# Balanced_Line_Receiver.net
KiCad netlist of a schematic drawn in Altium Designer
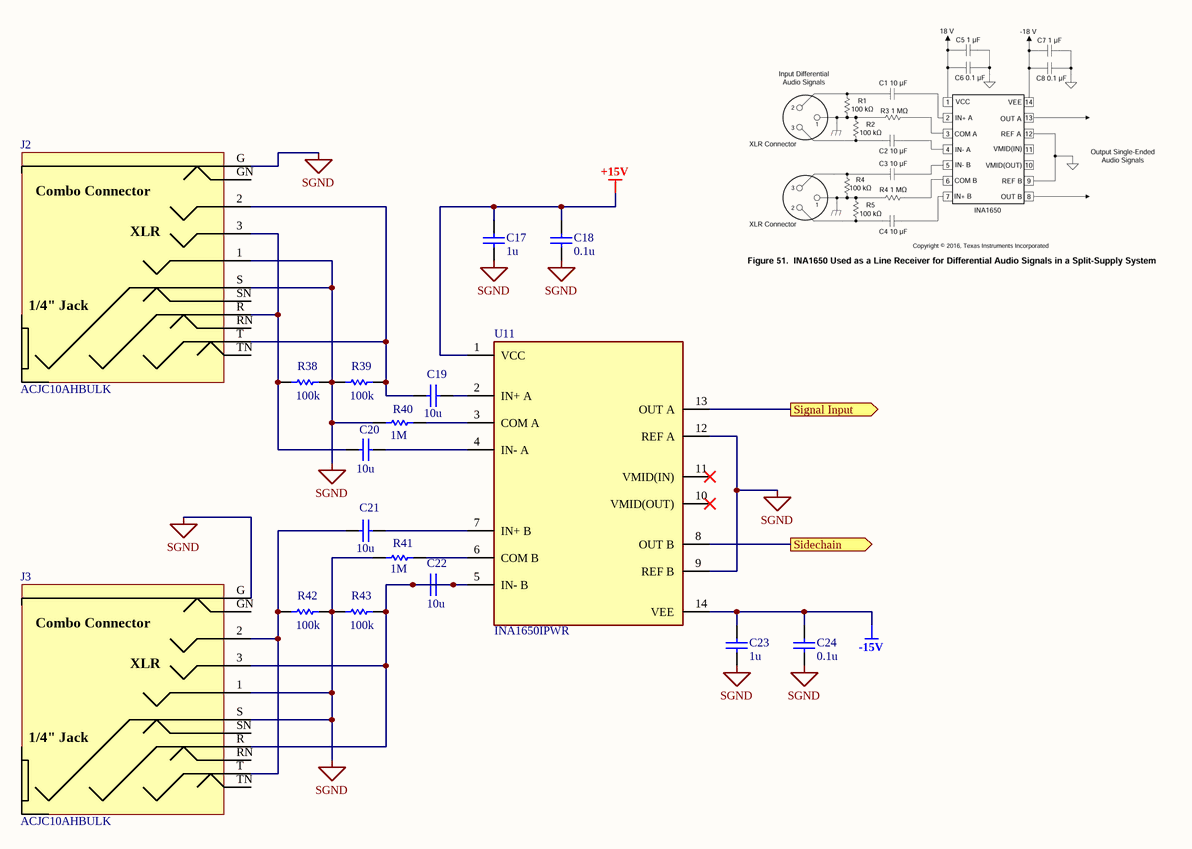
[diagram p0: Balanced Line Receiver.SchDoc]

(export (version "E")
  (design (tool "Eeschema 10.0.6"))
  (components
    (comp (ref "C17")
      (value "1u")
      (description "Capacitor")
      (libsource (lib "Simulation Generic Components") (part "Capacitor"))
    )
    (comp (ref "C18")
      (value "0.1u")
      (description "Capacitor")
      (libsource (lib "Simulation Generic Components") (part "Capacitor"))
    )
    (comp (ref "C19")
      (value "10u")
      (description "Capacitor")
      (libsource (lib "Simulation Generic Components") (part "Capacitor"))
    )
    (comp (ref "C20")
      (value "10u")
      (description "Capacitor")
      (libsource (lib "Simulation Generic Components") (part "Capacitor"))
    )
    (comp (ref "C21")
      (value "10u")
      (description "Capacitor")
      (libsource (lib "Simulation Generic Components") (part "Capacitor"))
    )
    (comp (ref "C22")
      (value "10u")
      (description "Capacitor")
      (libsource (lib "Simulation Generic Components") (part "Capacitor"))
    )
    (comp (ref "C23")
      (value "1u")
      (description "Capacitor")
      (libsource (lib "Simulation Generic Components") (part "Capacitor"))
    )
    (comp (ref "C24")
      (value "0.1u")
      (description "Capacitor")
      (libsource (lib "Simulation Generic Components") (part "Capacitor"))
    )
    (comp (ref "J2")
      (value "ACJC10AHBULK")
      (footprint "ACJC10AH")
      (description "Audio/RCA Connector, 10 Pole(s), Female, Solder Terminal, Latch, Receptacle")
      (fields (field (name "MANUFACTURER") "Amphenol"))
      (libsource (lib "DRC") (part "ACJC10AHBULK"))
    )
    (comp (ref "J3")
      (value "ACJC10AHBULK")
      (footprint "ACJC10AH")
      (description "Audio/RCA Connector, 10 Pole(s), Female, Solder Terminal, Latch, Receptacle")
      (fields (field (name "MANUFACTURER") "Amphenol"))
      (libsource (lib "DRC") (part "ACJC10AHBULK"))
    )
    (comp (ref "R38")
      (value "100k")
      (description "Resistor")
      (libsource (lib "Simulation Generic Components") (part "Resistor"))
    )
    (comp (ref "R39")
      (value "100k")
      (description "Resistor")
      (libsource (lib "Simulation Generic Components") (part "Resistor"))
    )
    (comp (ref "R40")
      (value "1M")
      (description "Resistor")
      (libsource (lib "Simulation Generic Components") (part "Resistor"))
    )
    (comp (ref "R41")
      (value "1M")
      (description "Resistor")
      (libsource (lib "Simulation Generic Components") (part "Resistor"))
    )
    (comp (ref "R42")
      (value "100k")
      (description "Resistor")
      (libsource (lib "Simulation Generic Components") (part "Resistor"))
    )
    (comp (ref "R43")
      (value "100k")
      (description "Resistor")
      (libsource (lib "Simulation Generic Components") (part "Resistor"))
    )
    (comp (ref "U11")
      (value "INA1650IPWR")
      (footprint "FP-PW0014A-IPC_C")
      (description "IC AUDIO RECEIVER 14TSSOP")
      (libsource (lib "DRC") (part "INA1650IPWR"))
    )
  )
  (nets
    (net (code "1") (name "+15V") (class "Default")
      (node (ref "C17") (pin "2") (pinfunction "2_2") (pintype "passive"))
      (node (ref "C18") (pin "2") (pinfunction "2_2") (pintype "passive"))
      (node (ref "U11") (pin "1") (pinfunction "VCC_1") (pintype "power_in"))
    )
    (net (code "2") (name "-15V") (class "Default")
      (node (ref "C23") (pin "2") (pinfunction "2_2") (pintype "passive"))
      (node (ref "C24") (pin "2") (pinfunction "2_2") (pintype "passive"))
      (node (ref "U11") (pin "14") (pinfunction "VEE_14") (pintype "power_in"))
    )
    (net (code "3") (name "/Sidechain") (class "Default")
      (node (ref "U11") (pin "8") (pinfunction "OUT_B_8") (pintype "passive"))
    )
    (net (code "4") (name "/Signal Input") (class "Default")
      (node (ref "U11") (pin "13") (pinfunction "OUT_A_13") (pintype "passive"))
    )
    (net (code "5") (name "Net-(C19-Pad2)") (class "Default")
      (node (ref "C19") (pin "2") (pinfunction "2_2") (pintype "passive"))
      (node (ref "J2") (pin "2") (pinfunction "2_2") (pintype "passive"))
      (node (ref "J2") (pin "T") (pinfunction "T_T") (pintype "passive"))
      (node (ref "R39") (pin "1") (pinfunction "1_1") (pintype "passive"))
    )
    (net (code "6") (name "Net-(C20-Pad2)") (class "Default")
      (node (ref "C20") (pin "2") (pinfunction "2_2") (pintype "passive"))
      (node (ref "J2") (pin "3") (pinfunction "3_3") (pintype "passive"))
      (node (ref "J2") (pin "R") (pinfunction "R_R") (pintype "passive"))
      (node (ref "R38") (pin "2") (pinfunction "2_2") (pintype "passive"))
    )
    (net (code "7") (name "Net-(C21-Pad2)") (class "Default")
      (node (ref "C21") (pin "2") (pinfunction "2_2") (pintype "passive"))
      (node (ref "J3") (pin "2") (pinfunction "2_2") (pintype "passive"))
      (node (ref "J3") (pin "T") (pinfunction "T_T") (pintype "passive"))
      (node (ref "R42") (pin "2") (pinfunction "2_2") (pintype "passive"))
    )
    (net (code "8") (name "Net-(U11-COM_A)") (class "Default")
      (node (ref "R40") (pin "1") (pinfunction "1_1") (pintype "passive"))
      (node (ref "U11") (pin "3") (pinfunction "COM_A_3") (pintype "passive"))
    )
    (net (code "9") (name "Net-(U11-COM_B)") (class "Default")
      (node (ref "R41") (pin "1") (pinfunction "1_1") (pintype "passive"))
      (node (ref "U11") (pin "6") (pinfunction "COM_B_6") (pintype "passive"))
    )
    (net (code "10") (name "Net-(U11-IN+_A)") (class "Default")
      (node (ref "C19") (pin "1") (pinfunction "1_1") (pintype "passive"))
      (node (ref "U11") (pin "2") (pinfunction "IN+_A_2") (pintype "tri_state"))
    )
    (net (code "11") (name "Net-(U11-IN+_B)") (class "Default")
      (node (ref "C21") (pin "1") (pinfunction "1_1") (pintype "passive"))
      (node (ref "U11") (pin "7") (pinfunction "IN+_B_7") (pintype "tri_state"))
    )
    (net (code "12") (name "Net-(U11-IN-_A)") (class "Default")
      (node (ref "C20") (pin "1") (pinfunction "1_1") (pintype "passive"))
      (node (ref "U11") (pin "4") (pinfunction "IN-_A_4") (pintype "tri_state"))
    )
    (net (code "13") (name "Net-(U11-IN-_B)") (class "Default")
      (node (ref "C22") (pin "1") (pinfunction "1_1") (pintype "passive"))
      (node (ref "C22") (pin "2") (pinfunction "2_2") (pintype "passive"))
      (node (ref "J3") (pin "3") (pinfunction "3_3") (pintype "passive"))
      (node (ref "J3") (pin "R") (pinfunction "R_R") (pintype "passive"))
      (node (ref "R43") (pin "1") (pinfunction "1_1") (pintype "passive"))
      (node (ref "U11") (pin "5") (pinfunction "IN-_B_5") (pintype "tri_state"))
    )
    (net (code "14") (name "SGND") (class "Default")
      (node (ref "C17") (pin "1") (pinfunction "1_1") (pintype "passive"))
      (node (ref "C18") (pin "1") (pinfunction "1_1") (pintype "passive"))
      (node (ref "C23") (pin "1") (pinfunction "1_1") (pintype "passive"))
      (node (ref "C24") (pin "1") (pinfunction "1_1") (pintype "passive"))
      (node (ref "J2") (pin "1") (pinfunction "1_1") (pintype "passive"))
      (node (ref "J2") (pin "G") (pinfunction "G_G") (pintype "passive"))
      (node (ref "J2") (pin "S") (pinfunction "S_S") (pintype "passive"))
      (node (ref "J3") (pin "1") (pinfunction "1_1") (pintype "passive"))
      (node (ref "J3") (pin "G") (pinfunction "G_G") (pintype "passive"))
      (node (ref "J3") (pin "S") (pinfunction "S_S") (pintype "passive"))
      (node (ref "R38") (pin "1") (pinfunction "1_1") (pintype "passive"))
      (node (ref "R39") (pin "2") (pinfunction "2_2") (pintype "passive"))
      (node (ref "R40") (pin "2") (pinfunction "2_2") (pintype "passive"))
      (node (ref "R41") (pin "2") (pinfunction "2_2") (pintype "passive"))
      (node (ref "R42") (pin "1") (pinfunction "1_1") (pintype "passive"))
      (node (ref "R43") (pin "2") (pinfunction "2_2") (pintype "passive"))
      (node (ref "U11") (pin "12") (pinfunction "REF_A_12") (pintype "passive"))
      (node (ref "U11") (pin "9") (pinfunction "REF_B_9") (pintype "passive"))
    )
    (net (code "15") (name "unconnected-(J2-PadGN)") (class "Default")
      (node (ref "J2") (pin "GN") (pinfunction "GN_GN") (pintype "passive"))
    )
    (net (code "16") (name "unconnected-(J2-PadRN)") (class "Default")
      (node (ref "J2") (pin "RN") (pinfunction "RN_RN") (pintype "passive"))
    )
    (net (code "17") (name "unconnected-(J2-PadSN)") (class "Default")
      (node (ref "J2") (pin "SN") (pinfunction "SN_SN") (pintype "passive"))
    )
    (net (code "18") (name "unconnected-(J2-PadTN)") (class "Default")
      (node (ref "J2") (pin "TN") (pinfunction "TN_TN") (pintype "passive"))
    )
    (net (code "19") (name "unconnected-(J3-PadGN)") (class "Default")
      (node (ref "J3") (pin "GN") (pinfunction "GN_GN") (pintype "passive"))
    )
    (net (code "20") (name "unconnected-(J3-PadRN)") (class "Default")
      (node (ref "J3") (pin "RN") (pinfunction "RN_RN") (pintype "passive"))
    )
    (net (code "21") (name "unconnected-(J3-PadSN)") (class "Default")
      (node (ref "J3") (pin "SN") (pinfunction "SN_SN") (pintype "passive"))
    )
    (net (code "22") (name "unconnected-(J3-PadTN)") (class "Default")
      (node (ref "J3") (pin "TN") (pinfunction "TN_TN") (pintype "passive"))
    )
    (net (code "23") (name "unconnected-(U11-VMID(IN)-Pad11)") (class "Default")
      (node (ref "U11") (pin "11") (pinfunction "VMID(IN)_11") (pintype "passive+no_connect"))
    )
    (net (code "24") (name "unconnected-(U11-VMID(OUT)-Pad10)") (class "Default")
      (node (ref "U11") (pin "10") (pinfunction "VMID(OUT)_10") (pintype "passive+no_connect"))
    )
  )
)
